# TSAL_Schematic.net
KiCad netlist of a schematic drawn in Altium Designer
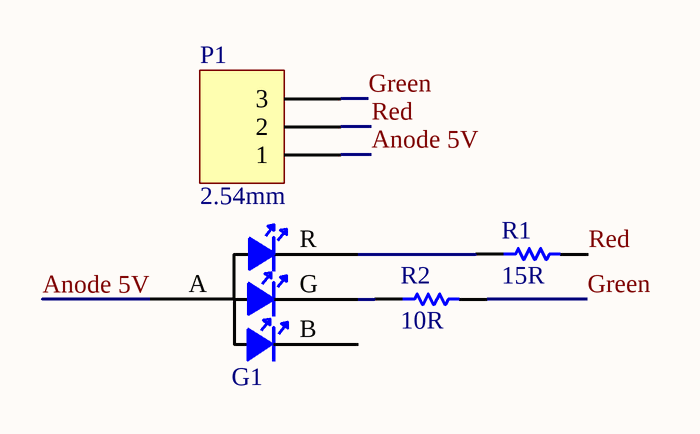
[diagram p0: TSAL_Schematic.SchDoc]

(export (version "E")
  (design (tool "Eeschema 10.0.6"))
  (components
    (comp (ref "G1")
      (value "G")
      (footprint "HOTRED RGB_LED")
      (libsource (lib "analogue") (part "LED - RGB (Anode Common)"))
    )
    (comp (ref "P1")
      (value "2.54mm")
      (footprint "TH 2.54mm Header 1x3")
      (fields (field (name "PART NUMBER") "TH 2.54mm Header 1x3") (field (name "CONTACT") "NA"))
      (libsource (lib "ts_20-standard-connectors") (part "Header 1x3"))
    )
    (comp (ref "R1")
      (value "15R")
      (footprint "2512")
      (fields
        (field (name "PART NUMBER") "352115RFT")
        (field (name "MANUFACTURER") "TE Connectivity")
        (field (name "TOLERANCE") "0.01")
      )
      (libsource (lib "ts_20-standard-library") (part "Resistor"))
    )
    (comp (ref "R2")
      (value "10R")
      (footprint "2512")
      (fields
        (field (name "PART NUMBER") "352110RFT")
        (field (name "MANUFACTURER") "TE Connectivity")
        (field (name "TOLERANCE") "0.01")
      )
      (libsource (lib "ts_20-standard-library") (part "Resistor"))
    )
  )
  (nets
    (net (code "1") (name "/Anode 5V") (class "Default")
      (node (ref "G1") (pin "A") (pinfunction "A_A") (pintype "passive"))
      (node (ref "P1") (pin "1") (pinfunction "1_1") (pintype "passive"))
    )
    (net (code "2") (name "/Green") (class "Default")
      (node (ref "P1") (pin "3") (pinfunction "3_3") (pintype "passive"))
      (node (ref "R2") (pin "2") (pinfunction "2_2") (pintype "passive"))
    )
    (net (code "3") (name "/Red") (class "Default")
      (node (ref "P1") (pin "2") (pinfunction "2_2") (pintype "passive"))
      (node (ref "R1") (pin "2") (pinfunction "2_2") (pintype "passive"))
    )
    (net (code "4") (name "Net-(G1-PadG)") (class "Default")
      (node (ref "G1") (pin "G") (pinfunction "G_G") (pintype "passive"))
      (node (ref "R2") (pin "1") (pinfunction "1_1") (pintype "passive"))
    )
    (net (code "5") (name "Net-(G1-PadR)") (class "Default")
      (node (ref "G1") (pin "R") (pinfunction "R_R") (pintype "passive"))
      (node (ref "R1") (pin "1") (pinfunction "1_1") (pintype "passive"))
    )
    (net (code "6") (name "unconnected-(G1-PadB)") (class "Default")
      (node (ref "G1") (pin "B") (pinfunction "B_B") (pintype "passive"))
    )
  )
)
